# schematicv2.net
KiCad netlist of a schematic drawn in EAGLE
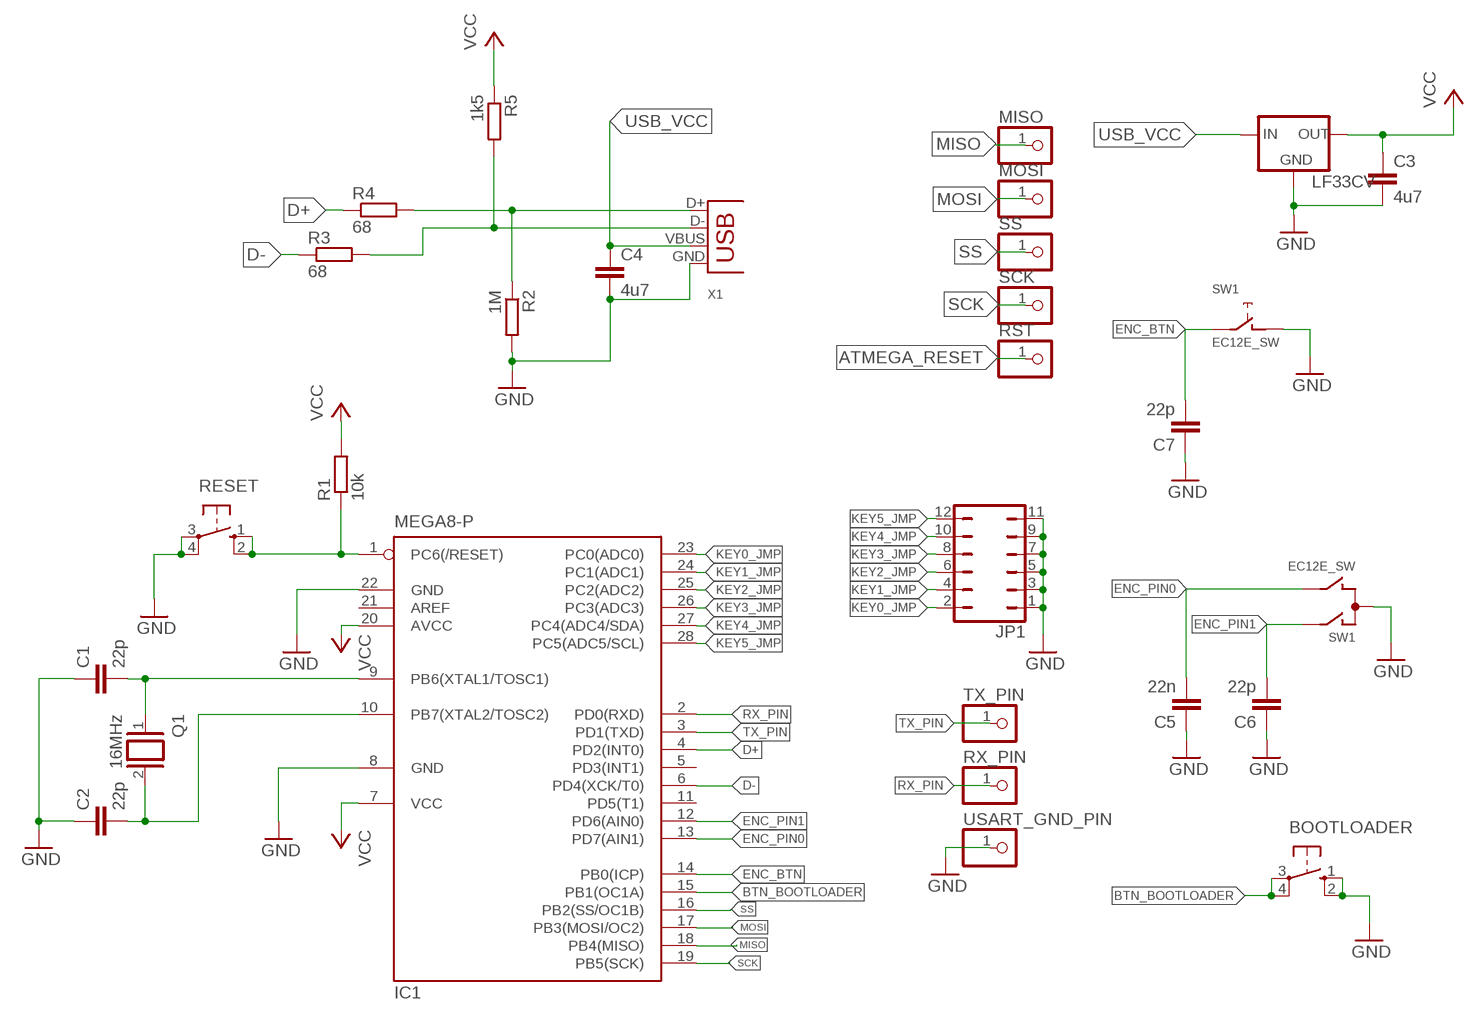
[diagram p0: schematic, sheet 1]

(export (version "E")
  (design (tool "Eeschema 10.0.6"))
  (components
    (comp (ref "BOOTLOADER")
      (value "10-XX")
      (footprint "eagle-import:B3F-10XX")
      (fields (field (name "MPN") "B3F-1000"))
      (libsource (lib "eagle-import") (part "10-XX"))
    )
    (comp (ref "C1")
      (value "22p")
      (footprint "eagle-import:C5B5")
      (libsource (lib "eagle-import") (part "C5/5"))
    )
    (comp (ref "C2")
      (value "22p")
      (footprint "eagle-import:C5B5")
      (libsource (lib "eagle-import") (part "C5/5"))
    )
    (comp (ref "C3")
      (value "4u7")
      (footprint "eagle-import:C5B3")
      (libsource (lib "eagle-import") (part "C5/3"))
    )
    (comp (ref "C4")
      (value "4u7")
      (footprint "eagle-import:C5B3")
      (libsource (lib "eagle-import") (part "C5/3"))
    )
    (comp (ref "C5")
      (value "22n")
      (footprint "eagle-import:C5B5")
      (libsource (lib "eagle-import") (part "C5/5"))
    )
    (comp (ref "C6")
      (value "22p")
      (footprint "eagle-import:C5B5")
      (libsource (lib "eagle-import") (part "C5/5"))
    )
    (comp (ref "C7")
      (value "22p")
      (footprint "eagle-import:C5B5")
      (libsource (lib "eagle-import") (part "C5/5"))
    )
    (comp (ref "IC1")
      (value "MEGA8-P")
      (footprint "eagle-import:DIL28-3")
      (libsource (lib "eagle-import") (part "MEGA8-P"))
    )
    (comp (ref "JP1")
      (value "JP6Q")
      (footprint "eagle-import:JP6Q")
      (libsource (lib "eagle-import") (part "JP6Q"))
    )
    (comp (ref "LF33CV")
      (value "LFXXCVS")
      (footprint "eagle-import:TO220S")
      (libsource (lib "eagle-import") (part "LFXXCVS"))
    )
    (comp (ref "MISO")
      (value "PINHD-1X1")
      (footprint "eagle-import:1X01")
      (libsource (lib "eagle-import") (part "PINHD-1X1"))
    )
    (comp (ref "MOSI")
      (value "PINHD-1X1")
      (footprint "eagle-import:1X01")
      (libsource (lib "eagle-import") (part "PINHD-1X1"))
    )
    (comp (ref "Q1")
      (value "16MHz")
      (footprint "eagle-import:QS")
      (libsource (lib "eagle-import") (part "XTAL/S"))
    )
    (comp (ref "R1")
      (value "10k")
      (footprint "eagle-import:0309V")
      (libsource (lib "eagle-import") (part "R-EU_0309/V"))
    )
    (comp (ref "R2")
      (value "1M")
      (footprint "eagle-import:0204_7")
      (libsource (lib "eagle-import") (part "R-EU_0204/7"))
    )
    (comp (ref "R3")
      (value "68")
      (footprint "eagle-import:0204_7")
      (libsource (lib "eagle-import") (part "R-EU_0204/7"))
    )
    (comp (ref "R4")
      (value "68")
      (footprint "eagle-import:0204_7")
      (libsource (lib "eagle-import") (part "R-EU_0204/7"))
    )
    (comp (ref "R5")
      (value "1k5")
      (footprint "eagle-import:0204_7")
      (libsource (lib "eagle-import") (part "R-EU_0204/7"))
    )
    (comp (ref "RESET")
      (value "10-XX")
      (footprint "eagle-import:B3F-10XX")
      (fields (field (name "MPN") "B3F-1000"))
      (libsource (lib "eagle-import") (part "10-XX"))
    )
    (comp (ref "RST")
      (value "PINHD-1X1")
      (footprint "eagle-import:1X01")
      (libsource (lib "eagle-import") (part "PINHD-1X1"))
    )
    (comp (ref "RX_PIN")
      (value "PINHD-1X1")
      (footprint "eagle-import:1X01")
      (libsource (lib "eagle-import") (part "PINHD-1X1"))
    )
    (comp (ref "SCK")
      (value "PINHD-1X1")
      (footprint "eagle-import:1X01")
      (libsource (lib "eagle-import") (part "PINHD-1X1"))
    )
    (comp (ref "SS")
      (value "PINHD-1X1")
      (footprint "eagle-import:1X01")
      (libsource (lib "eagle-import") (part "PINHD-1X1"))
    )
    (comp (ref "SW1")
      (value "EC12E_SW")
      (footprint "eagle-import:ALPS_EC12E_SW")
      (libsource (lib "eagle-import") (part "EC12E_SW"))
    )
    (comp (ref "TX_PIN")
      (value "PINHD-1X1")
      (footprint "eagle-import:1X01")
      (libsource (lib "eagle-import") (part "PINHD-1X1"))
    )
    (comp (ref "USART_GND_PIN")
      (value "PINHD-1X1")
      (footprint "eagle-import:1X01")
      (libsource (lib "eagle-import") (part "PINHD-1X1"))
    )
    (comp (ref "X1")
      (value "USB-B-H")
      (footprint "eagle-import:USB-B-H")
      (libsource (lib "eagle-import") (part "USB-B-H"))
    )
  )
  (nets
    (net (code "1") (name "ATMEGA_RESET") (class "Default")
      (node (ref "IC1") (pin "1") (pinfunction "PC6(/RESET)_1") (pintype "bidirectional"))
      (node (ref "R1") (pin "1") (pinfunction "1_1") (pintype "passive"))
      (node (ref "RESET") (pin "1") (pinfunction "S_1") (pintype "passive"))
      (node (ref "RESET") (pin "2") (pinfunction "S1_2") (pintype "passive"))
      (node (ref "RST") (pin "1") (pinfunction "1_1") (pintype "passive"))
    )
    (net (code "2") (name "BTN_BOOTLOADER") (class "Default")
      (node (ref "BOOTLOADER") (pin "3") (pinfunction "P_3") (pintype "passive"))
      (node (ref "BOOTLOADER") (pin "4") (pinfunction "P1_4") (pintype "passive"))
      (node (ref "IC1") (pin "15") (pinfunction "PB1(OC1A)_15") (pintype "bidirectional"))
    )
    (net (code "3") (name "D+") (class "Default")
      (node (ref "IC1") (pin "4") (pinfunction "PD2(INT0)_4") (pintype "bidirectional"))
      (node (ref "R4") (pin "1") (pinfunction "1_1") (pintype "passive"))
    )
    (net (code "4") (name "D-") (class "Default")
      (node (ref "IC1") (pin "6") (pinfunction "PD4(XCK/T0)_6") (pintype "bidirectional"))
      (node (ref "R3") (pin "1") (pinfunction "1_1") (pintype "passive"))
    )
    (net (code "5") (name "ENC_BTN") (class "Default")
      (node (ref "C7") (pin "2") (pinfunction "2_2") (pintype "passive"))
      (node (ref "IC1") (pin "14") (pinfunction "PB0(ICP)_14") (pintype "bidirectional"))
      (node (ref "SW1") (pin "E") (pinfunction "2_E") (pintype "passive"))
    )
    (net (code "6") (name "ENC_PIN0") (class "Default")
      (node (ref "C5") (pin "2") (pinfunction "2_2") (pintype "passive"))
      (node (ref "IC1") (pin "13") (pinfunction "PD7(AIN1)_13") (pintype "bidirectional"))
      (node (ref "SW1") (pin "B") (pinfunction "B_B") (pintype "passive"))
    )
    (net (code "7") (name "ENC_PIN1") (class "Default")
      (node (ref "C6") (pin "2") (pinfunction "2_2") (pintype "passive"))
      (node (ref "IC1") (pin "12") (pinfunction "PD6(AIN0)_12") (pintype "bidirectional"))
      (node (ref "SW1") (pin "A") (pinfunction "A_A") (pintype "passive"))
    )
    (net (code "8") (name "GND") (class "Default")
      (node (ref "BOOTLOADER") (pin "1") (pinfunction "S_1") (pintype "passive"))
      (node (ref "BOOTLOADER") (pin "2") (pinfunction "S1_2") (pintype "passive"))
      (node (ref "C1") (pin "1") (pinfunction "1_1") (pintype "passive"))
      (node (ref "C2") (pin "1") (pinfunction "1_1") (pintype "passive"))
      (node (ref "C3") (pin "2") (pinfunction "2_2") (pintype "passive"))
      (node (ref "C4") (pin "2") (pinfunction "2_2") (pintype "passive"))
      (node (ref "C5") (pin "1") (pinfunction "1_1") (pintype "passive"))
      (node (ref "C6") (pin "1") (pinfunction "1_1") (pintype "passive"))
      (node (ref "C7") (pin "1") (pinfunction "1_1") (pintype "passive"))
      (node (ref "IC1") (pin "22") (pinfunction "GND_22") (pintype "power_in"))
      (node (ref "IC1") (pin "8") (pinfunction "GND_8") (pintype "power_in"))
      (node (ref "JP1") (pin "1") (pinfunction "1_1") (pintype "passive"))
      (node (ref "JP1") (pin "11") (pinfunction "11_11") (pintype "passive"))
      (node (ref "JP1") (pin "3") (pinfunction "3_3") (pintype "passive"))
      (node (ref "JP1") (pin "5") (pinfunction "5_5") (pintype "passive"))
      (node (ref "JP1") (pin "7") (pinfunction "7_7") (pintype "passive"))
      (node (ref "JP1") (pin "9") (pinfunction "9_9") (pintype "passive"))
      (node (ref "LF33CV") (pin "2") (pinfunction "GND_2") (pintype "input"))
      (node (ref "R2") (pin "2") (pinfunction "2_2") (pintype "passive"))
      (node (ref "RESET") (pin "3") (pinfunction "P_3") (pintype "passive"))
      (node (ref "RESET") (pin "4") (pinfunction "P1_4") (pintype "passive"))
      (node (ref "SW1") (pin "C") (pinfunction "C_C") (pintype "passive"))
      (node (ref "SW1") (pin "D") (pinfunction "1_D") (pintype "passive"))
      (node (ref "USART_GND_PIN") (pin "1") (pinfunction "1_1") (pintype "passive"))
      (node (ref "X1") (pin "GND") (pinfunction "GND_GND") (pintype "bidirectional"))
    )
    (net (code "9") (name "KEY0_JMP") (class "Default")
      (node (ref "IC1") (pin "23") (pinfunction "PC0(ADC0)_23") (pintype "bidirectional"))
      (node (ref "JP1") (pin "2") (pinfunction "2_2") (pintype "passive"))
    )
    (net (code "10") (name "KEY1_JMP") (class "Default")
      (node (ref "IC1") (pin "24") (pinfunction "PC1(ADC1)_24") (pintype "bidirectional"))
      (node (ref "JP1") (pin "4") (pinfunction "4_4") (pintype "passive"))
    )
    (net (code "11") (name "KEY2_JMP") (class "Default")
      (node (ref "IC1") (pin "25") (pinfunction "PC2(ADC2)_25") (pintype "bidirectional"))
      (node (ref "JP1") (pin "6") (pinfunction "6_6") (pintype "passive"))
    )
    (net (code "12") (name "KEY3_JMP") (class "Default")
      (node (ref "IC1") (pin "26") (pinfunction "PC3(ADC3)_26") (pintype "bidirectional"))
      (node (ref "JP1") (pin "8") (pinfunction "8_8") (pintype "passive"))
    )
    (net (code "13") (name "KEY4_JMP") (class "Default")
      (node (ref "IC1") (pin "27") (pinfunction "PC4(ADC4/SDA)_27") (pintype "bidirectional"))
      (node (ref "JP1") (pin "10") (pinfunction "10_10") (pintype "passive"))
    )
    (net (code "14") (name "KEY5_JMP") (class "Default")
      (node (ref "IC1") (pin "28") (pinfunction "PC5(ADC5/SCL)_28") (pintype "bidirectional"))
      (node (ref "JP1") (pin "12") (pinfunction "12_12") (pintype "passive"))
    )
    (net (code "15") (name "MISO") (class "Default")
      (node (ref "IC1") (pin "18") (pinfunction "PB4(MISO)_18") (pintype "bidirectional"))
      (node (ref "MISO") (pin "1") (pinfunction "1_1") (pintype "passive"))
    )
    (net (code "16") (name "MOSI") (class "Default")
      (node (ref "IC1") (pin "17") (pinfunction "PB3(MOSI/OC2)_17") (pintype "bidirectional"))
      (node (ref "MOSI") (pin "1") (pinfunction "1_1") (pintype "passive"))
    )
    (net (code "17") (name "Net-(IC1-PB6(XTAL1{slash}TOSC1))") (class "Default")
      (node (ref "C1") (pin "2") (pinfunction "2_2") (pintype "passive"))
      (node (ref "IC1") (pin "9") (pinfunction "PB6(XTAL1/TOSC1)_9") (pintype "bidirectional"))
      (node (ref "Q1") (pin "1") (pinfunction "1_1") (pintype "passive"))
    )
    (net (code "18") (name "Net-(IC1-PB7(XTAL2{slash}TOSC2))") (class "Default")
      (node (ref "C2") (pin "2") (pinfunction "2_2") (pintype "passive"))
      (node (ref "IC1") (pin "10") (pinfunction "PB7(XTAL2/TOSC2)_10") (pintype "bidirectional"))
      (node (ref "Q1") (pin "2") (pinfunction "2_2") (pintype "passive"))
    )
    (net (code "19") (name "Net-(R2-Pad1)") (class "Default")
      (node (ref "R2") (pin "1") (pinfunction "1_1") (pintype "passive"))
      (node (ref "R4") (pin "2") (pinfunction "2_2") (pintype "passive"))
      (node (ref "X1") (pin "D+") (pinfunction "D+_D+") (pintype "bidirectional"))
    )
    (net (code "20") (name "Net-(R3-Pad2)") (class "Default")
      (node (ref "R3") (pin "2") (pinfunction "2_2") (pintype "passive"))
      (node (ref "R5") (pin "2") (pinfunction "2_2") (pintype "passive"))
      (node (ref "X1") (pin "D-") (pinfunction "D-_D-") (pintype "bidirectional"))
    )
    (net (code "21") (name "RX_PIN") (class "Default")
      (node (ref "IC1") (pin "2") (pinfunction "PD0(RXD)_2") (pintype "bidirectional"))
      (node (ref "RX_PIN") (pin "1") (pinfunction "1_1") (pintype "passive"))
    )
    (net (code "22") (name "SCK") (class "Default")
      (node (ref "IC1") (pin "19") (pinfunction "PB5(SCK)_19") (pintype "bidirectional"))
      (node (ref "SCK") (pin "1") (pinfunction "1_1") (pintype "passive"))
    )
    (net (code "23") (name "SS") (class "Default")
      (node (ref "IC1") (pin "16") (pinfunction "PB2(SS/OC1B)_16") (pintype "bidirectional"))
      (node (ref "SS") (pin "1") (pinfunction "1_1") (pintype "passive"))
    )
    (net (code "24") (name "TX_PIN") (class "Default")
      (node (ref "IC1") (pin "3") (pinfunction "PD1(TXD)_3") (pintype "bidirectional"))
      (node (ref "TX_PIN") (pin "1") (pinfunction "1_1") (pintype "passive"))
    )
    (net (code "25") (name "USB_VCC") (class "Default")
      (node (ref "C4") (pin "1") (pinfunction "1_1") (pintype "passive"))
      (node (ref "LF33CV") (pin "1") (pinfunction "IN_1") (pintype "input"))
      (node (ref "X1") (pin "VBUS") (pinfunction "VBUS_VBUS") (pintype "bidirectional"))
    )
    (net (code "26") (name "VCC") (class "Default")
      (node (ref "C3") (pin "1") (pinfunction "1_1") (pintype "passive"))
      (node (ref "IC1") (pin "20") (pinfunction "AVCC_20") (pintype "power_in"))
      (node (ref "IC1") (pin "7") (pinfunction "VCC_7") (pintype "power_in"))
      (node (ref "LF33CV") (pin "3") (pinfunction "OUT_3") (pintype "passive"))
      (node (ref "R1") (pin "2") (pinfunction "2_2") (pintype "passive"))
      (node (ref "R5") (pin "1") (pinfunction "1_1") (pintype "passive"))
    )
    (net (code "27") (name "unconnected-(IC1-AREF-Pad21)") (class "Default")
      (node (ref "IC1") (pin "21") (pinfunction "AREF_21") (pintype "passive"))
    )
    (net (code "28") (name "unconnected-(IC1-PD3(INT1)-Pad5)") (class "Default")
      (node (ref "IC1") (pin "5") (pinfunction "PD3(INT1)_5") (pintype "bidirectional"))
    )
    (net (code "29") (name "unconnected-(IC1-PD5(T1)-Pad11)") (class "Default")
      (node (ref "IC1") (pin "11") (pinfunction "PD5(T1)_11") (pintype "bidirectional"))
    )
  )
)
